# rev1.net
KiCad netlist of a schematic drawn in EAGLE
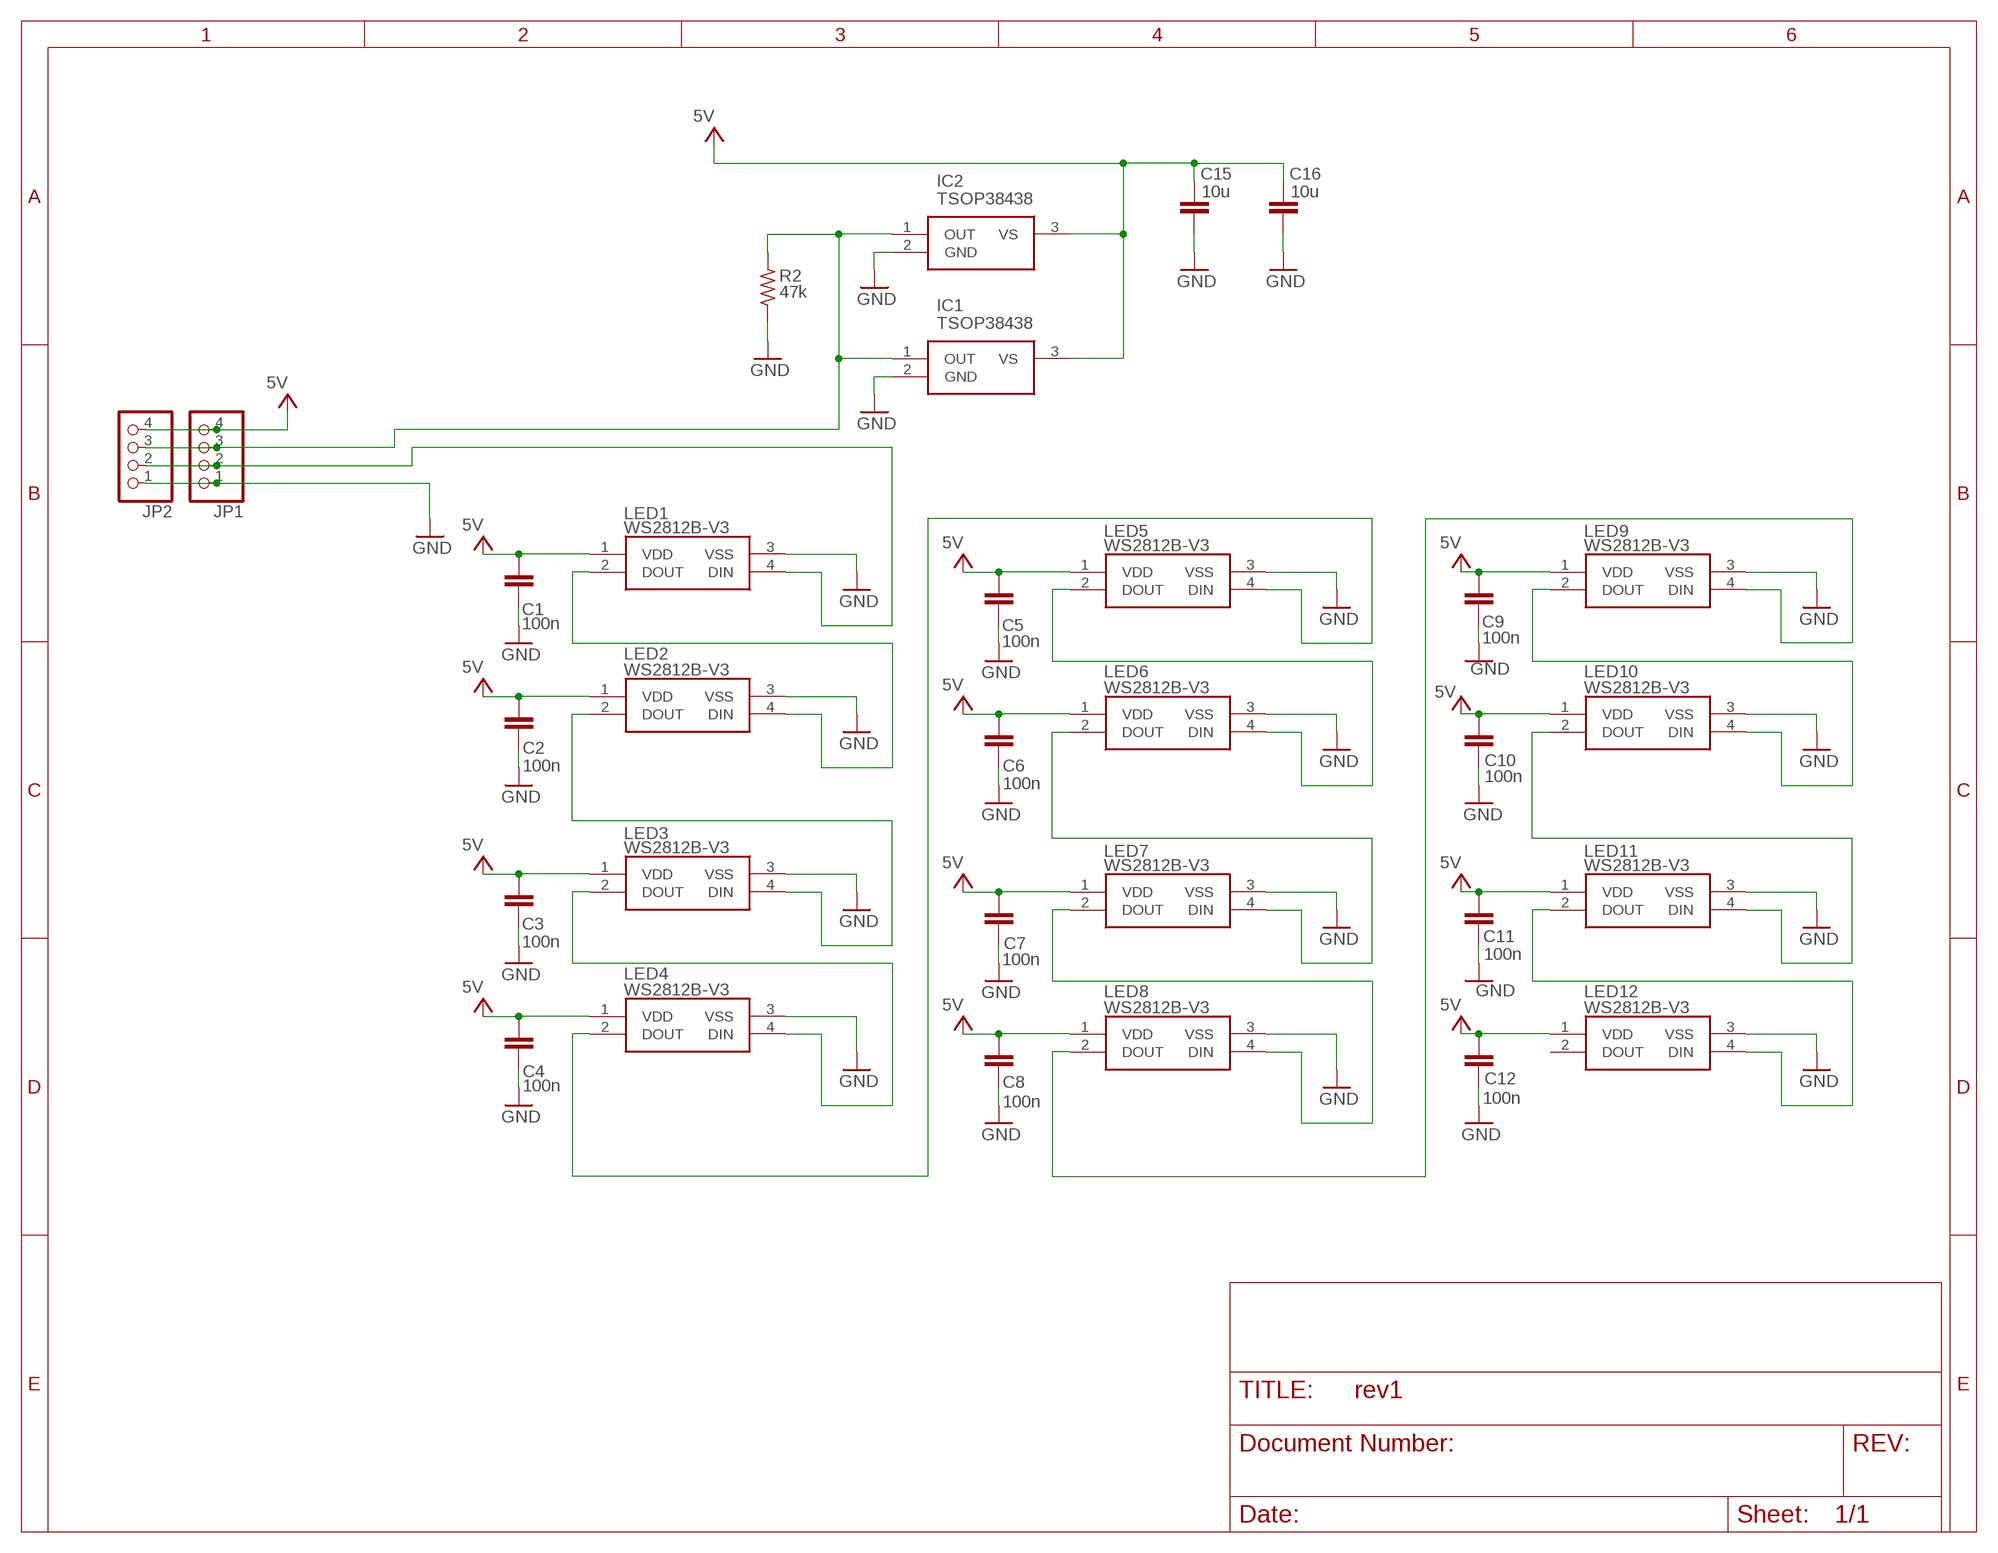
[diagram p0: schematic, sheet 1]

(export (version "E")
  (design (tool "Eeschema 10.0.6"))
  (components
    (comp (ref "C1")
      (value "100n")
      (footprint "eagle-import:C0805")
      (libsource (lib "eagle-import") (part "CAP_SMD0805"))
    )
    (comp (ref "C2")
      (value "100n")
      (footprint "eagle-import:C0805")
      (libsource (lib "eagle-import") (part "CAP_SMD0805"))
    )
    (comp (ref "C3")
      (value "100n")
      (footprint "eagle-import:C0805")
      (libsource (lib "eagle-import") (part "CAP_SMD0805"))
    )
    (comp (ref "C4")
      (value "100n")
      (footprint "eagle-import:C0805")
      (libsource (lib "eagle-import") (part "CAP_SMD0805"))
    )
    (comp (ref "C5")
      (value "100n")
      (footprint "eagle-import:C0805")
      (libsource (lib "eagle-import") (part "CAP_SMD0805"))
    )
    (comp (ref "C6")
      (value "100n")
      (footprint "eagle-import:C0805")
      (libsource (lib "eagle-import") (part "CAP_SMD0805"))
    )
    (comp (ref "C7")
      (value "100n")
      (footprint "eagle-import:C0805")
      (libsource (lib "eagle-import") (part "CAP_SMD0805"))
    )
    (comp (ref "C8")
      (value "100n")
      (footprint "eagle-import:C0805")
      (libsource (lib "eagle-import") (part "CAP_SMD0805"))
    )
    (comp (ref "C9")
      (value "100n")
      (footprint "eagle-import:C0805")
      (libsource (lib "eagle-import") (part "CAP_SMD0805"))
    )
    (comp (ref "C10")
      (value "100n")
      (footprint "eagle-import:C0805")
      (libsource (lib "eagle-import") (part "CAP_SMD0805"))
    )
    (comp (ref "C11")
      (value "100n")
      (footprint "eagle-import:C0805")
      (libsource (lib "eagle-import") (part "CAP_SMD0805"))
    )
    (comp (ref "C12")
      (value "100n")
      (footprint "eagle-import:C0805")
      (libsource (lib "eagle-import") (part "CAP_SMD0805"))
    )
    (comp (ref "C15")
      (value "10u")
      (footprint "eagle-import:C0805")
      (libsource (lib "eagle-import") (part "CAP_SMD0805"))
    )
    (comp (ref "C16")
      (value "10u")
      (footprint "eagle-import:C0805")
      (libsource (lib "eagle-import") (part "CAP_SMD0805"))
    )
    (comp (ref "IC1")
      (value "TSOP38438")
      (footprint "eagle-import:TSOP38238")
      (fields (field (name "MOUSER_PART_NUMBER") "78-TSOP38438") (field (name "RS_PART_NUMBER") "7085092P"))
      (libsource (lib "eagle-import") (part "TSOP38438"))
    )
    (comp (ref "IC2")
      (value "TSOP38438")
      (footprint "eagle-import:TSOP38238")
      (fields (field (name "MOUSER_PART_NUMBER") "78-TSOP38438") (field (name "RS_PART_NUMBER") "7085092P"))
      (libsource (lib "eagle-import") (part "TSOP38438"))
    )
    (comp (ref "JP1")
      (value "PINHD-1X4")
      (footprint "eagle-import:1X04")
      (libsource (lib "eagle-import") (part "PINHD-1X4"))
    )
    (comp (ref "JP2")
      (value "PINHD-1X4")
      (footprint "eagle-import:1X04")
      (libsource (lib "eagle-import") (part "PINHD-1X4"))
    )
    (comp (ref "LED1")
      (value "WS2812B-V3")
      (footprint "eagle-import:WS2812BV3")
      (libsource (lib "eagle-import") (part "WS2812B-V3"))
    )
    (comp (ref "LED2")
      (value "WS2812B-V3")
      (footprint "eagle-import:WS2812BV3")
      (libsource (lib "eagle-import") (part "WS2812B-V3"))
    )
    (comp (ref "LED3")
      (value "WS2812B-V3")
      (footprint "eagle-import:WS2812BV3")
      (libsource (lib "eagle-import") (part "WS2812B-V3"))
    )
    (comp (ref "LED4")
      (value "WS2812B-V3")
      (footprint "eagle-import:WS2812BV3")
      (libsource (lib "eagle-import") (part "WS2812B-V3"))
    )
    (comp (ref "LED5")
      (value "WS2812B-V3")
      (footprint "eagle-import:WS2812BV3")
      (libsource (lib "eagle-import") (part "WS2812B-V3"))
    )
    (comp (ref "LED6")
      (value "WS2812B-V3")
      (footprint "eagle-import:WS2812BV3")
      (libsource (lib "eagle-import") (part "WS2812B-V3"))
    )
    (comp (ref "LED7")
      (value "WS2812B-V3")
      (footprint "eagle-import:WS2812BV3")
      (libsource (lib "eagle-import") (part "WS2812B-V3"))
    )
    (comp (ref "LED8")
      (value "WS2812B-V3")
      (footprint "eagle-import:WS2812BV3")
      (libsource (lib "eagle-import") (part "WS2812B-V3"))
    )
    (comp (ref "LED9")
      (value "WS2812B-V3")
      (footprint "eagle-import:WS2812BV3")
      (libsource (lib "eagle-import") (part "WS2812B-V3"))
    )
    (comp (ref "LED10")
      (value "WS2812B-V3")
      (footprint "eagle-import:WS2812BV3")
      (libsource (lib "eagle-import") (part "WS2812B-V3"))
    )
    (comp (ref "LED11")
      (value "WS2812B-V3")
      (footprint "eagle-import:WS2812BV3")
      (libsource (lib "eagle-import") (part "WS2812B-V3"))
    )
    (comp (ref "LED12")
      (value "WS2812B-V3")
      (footprint "eagle-import:WS2812BV3")
      (libsource (lib "eagle-import") (part "WS2812B-V3"))
    )
    (comp (ref "R2")
      (value "47k")
      (footprint "eagle-import:R0805")
      (libsource (lib "eagle-import") (part "RES_SMD0805"))
    )
  )
  (nets
    (net (code "1") (name "5V") (class "Default")
      (node (ref "C1") (pin "2") (pinfunction "2_2") (pintype "passive"))
      (node (ref "C10") (pin "1") (pinfunction "1_1") (pintype "passive"))
      (node (ref "C11") (pin "2") (pinfunction "2_2") (pintype "passive"))
      (node (ref "C12") (pin "1") (pinfunction "1_1") (pintype "passive"))
      (node (ref "C15") (pin "2") (pinfunction "2_2") (pintype "passive"))
      (node (ref "C16") (pin "2") (pinfunction "2_2") (pintype "passive"))
      (node (ref "C2") (pin "1") (pinfunction "1_1") (pintype "passive"))
      (node (ref "C3") (pin "2") (pinfunction "2_2") (pintype "passive"))
      (node (ref "C4") (pin "1") (pinfunction "1_1") (pintype "passive"))
      (node (ref "C5") (pin "2") (pinfunction "2_2") (pintype "passive"))
      (node (ref "C6") (pin "1") (pinfunction "1_1") (pintype "passive"))
      (node (ref "C7") (pin "2") (pinfunction "2_2") (pintype "passive"))
      (node (ref "C8") (pin "1") (pinfunction "1_1") (pintype "passive"))
      (node (ref "C9") (pin "2") (pinfunction "2_2") (pintype "passive"))
      (node (ref "IC1") (pin "3") (pinfunction "VS_3") (pintype "bidirectional"))
      (node (ref "IC2") (pin "3") (pinfunction "VS_3") (pintype "bidirectional"))
      (node (ref "JP1") (pin "4") (pinfunction "4_4") (pintype "passive"))
      (node (ref "JP2") (pin "4") (pinfunction "4_4") (pintype "passive"))
      (node (ref "LED1") (pin "1") (pinfunction "VDD_1") (pintype "bidirectional"))
      (node (ref "LED10") (pin "1") (pinfunction "VDD_1") (pintype "bidirectional"))
      (node (ref "LED11") (pin "1") (pinfunction "VDD_1") (pintype "bidirectional"))
      (node (ref "LED12") (pin "1") (pinfunction "VDD_1") (pintype "bidirectional"))
      (node (ref "LED2") (pin "1") (pinfunction "VDD_1") (pintype "bidirectional"))
      (node (ref "LED3") (pin "1") (pinfunction "VDD_1") (pintype "bidirectional"))
      (node (ref "LED4") (pin "1") (pinfunction "VDD_1") (pintype "bidirectional"))
      (node (ref "LED5") (pin "1") (pinfunction "VDD_1") (pintype "bidirectional"))
      (node (ref "LED6") (pin "1") (pinfunction "VDD_1") (pintype "bidirectional"))
      (node (ref "LED7") (pin "1") (pinfunction "VDD_1") (pintype "bidirectional"))
      (node (ref "LED8") (pin "1") (pinfunction "VDD_1") (pintype "bidirectional"))
      (node (ref "LED9") (pin "1") (pinfunction "VDD_1") (pintype "bidirectional"))
    )
    (net (code "2") (name "GND") (class "Default")
      (node (ref "C1") (pin "1") (pinfunction "1_1") (pintype "passive"))
      (node (ref "C10") (pin "2") (pinfunction "2_2") (pintype "passive"))
      (node (ref "C11") (pin "1") (pinfunction "1_1") (pintype "passive"))
      (node (ref "C12") (pin "2") (pinfunction "2_2") (pintype "passive"))
      (node (ref "C15") (pin "1") (pinfunction "1_1") (pintype "passive"))
      (node (ref "C16") (pin "1") (pinfunction "1_1") (pintype "passive"))
      (node (ref "C2") (pin "2") (pinfunction "2_2") (pintype "passive"))
      (node (ref "C3") (pin "1") (pinfunction "1_1") (pintype "passive"))
      (node (ref "C4") (pin "2") (pinfunction "2_2") (pintype "passive"))
      (node (ref "C5") (pin "1") (pinfunction "1_1") (pintype "passive"))
      (node (ref "C6") (pin "2") (pinfunction "2_2") (pintype "passive"))
      (node (ref "C7") (pin "1") (pinfunction "1_1") (pintype "passive"))
      (node (ref "C8") (pin "2") (pinfunction "2_2") (pintype "passive"))
      (node (ref "C9") (pin "1") (pinfunction "1_1") (pintype "passive"))
      (node (ref "IC1") (pin "2") (pinfunction "GND_2") (pintype "bidirectional"))
      (node (ref "IC2") (pin "2") (pinfunction "GND_2") (pintype "bidirectional"))
      (node (ref "JP1") (pin "1") (pinfunction "1_1") (pintype "passive"))
      (node (ref "JP2") (pin "1") (pinfunction "1_1") (pintype "passive"))
      (node (ref "LED1") (pin "3") (pinfunction "VSS_3") (pintype "bidirectional"))
      (node (ref "LED10") (pin "3") (pinfunction "VSS_3") (pintype "bidirectional"))
      (node (ref "LED11") (pin "3") (pinfunction "VSS_3") (pintype "bidirectional"))
      (node (ref "LED12") (pin "3") (pinfunction "VSS_3") (pintype "bidirectional"))
      (node (ref "LED2") (pin "3") (pinfunction "VSS_3") (pintype "bidirectional"))
      (node (ref "LED3") (pin "3") (pinfunction "VSS_3") (pintype "bidirectional"))
      (node (ref "LED4") (pin "3") (pinfunction "VSS_3") (pintype "bidirectional"))
      (node (ref "LED5") (pin "3") (pinfunction "VSS_3") (pintype "bidirectional"))
      (node (ref "LED6") (pin "3") (pinfunction "VSS_3") (pintype "bidirectional"))
      (node (ref "LED7") (pin "3") (pinfunction "VSS_3") (pintype "bidirectional"))
      (node (ref "LED8") (pin "3") (pinfunction "VSS_3") (pintype "bidirectional"))
      (node (ref "LED9") (pin "3") (pinfunction "VSS_3") (pintype "bidirectional"))
      (node (ref "R2") (pin "1") (pinfunction "1_1") (pintype "passive"))
    )
    (net (code "3") (name "Net-(IC1-OUT)") (class "Default")
      (node (ref "IC1") (pin "1") (pinfunction "OUT_1") (pintype "bidirectional"))
      (node (ref "IC2") (pin "1") (pinfunction "OUT_1") (pintype "bidirectional"))
      (node (ref "JP1") (pin "3") (pinfunction "3_3") (pintype "passive"))
      (node (ref "JP2") (pin "3") (pinfunction "3_3") (pintype "passive"))
      (node (ref "R2") (pin "2") (pinfunction "2_2") (pintype "passive"))
    )
    (net (code "4") (name "Net-(LED1-DIN)") (class "Default")
      (node (ref "JP1") (pin "2") (pinfunction "2_2") (pintype "passive"))
      (node (ref "JP2") (pin "2") (pinfunction "2_2") (pintype "passive"))
      (node (ref "LED1") (pin "4") (pinfunction "DIN_4") (pintype "bidirectional"))
    )
    (net (code "5") (name "Net-(LED1-DOUT)") (class "Default")
      (node (ref "LED1") (pin "2") (pinfunction "DOUT_2") (pintype "bidirectional"))
      (node (ref "LED2") (pin "4") (pinfunction "DIN_4") (pintype "bidirectional"))
    )
    (net (code "6") (name "Net-(LED2-DOUT)") (class "Default")
      (node (ref "LED2") (pin "2") (pinfunction "DOUT_2") (pintype "bidirectional"))
      (node (ref "LED3") (pin "4") (pinfunction "DIN_4") (pintype "bidirectional"))
    )
    (net (code "7") (name "Net-(LED3-DOUT)") (class "Default")
      (node (ref "LED3") (pin "2") (pinfunction "DOUT_2") (pintype "bidirectional"))
      (node (ref "LED4") (pin "4") (pinfunction "DIN_4") (pintype "bidirectional"))
    )
    (net (code "8") (name "Net-(LED4-DOUT)") (class "Default")
      (node (ref "LED4") (pin "2") (pinfunction "DOUT_2") (pintype "bidirectional"))
      (node (ref "LED5") (pin "4") (pinfunction "DIN_4") (pintype "bidirectional"))
    )
    (net (code "9") (name "Net-(LED5-DOUT)") (class "Default")
      (node (ref "LED5") (pin "2") (pinfunction "DOUT_2") (pintype "bidirectional"))
      (node (ref "LED6") (pin "4") (pinfunction "DIN_4") (pintype "bidirectional"))
    )
    (net (code "10") (name "Net-(LED6-DOUT)") (class "Default")
      (node (ref "LED6") (pin "2") (pinfunction "DOUT_2") (pintype "bidirectional"))
      (node (ref "LED7") (pin "4") (pinfunction "DIN_4") (pintype "bidirectional"))
    )
    (net (code "11") (name "Net-(LED7-DOUT)") (class "Default")
      (node (ref "LED7") (pin "2") (pinfunction "DOUT_2") (pintype "bidirectional"))
      (node (ref "LED8") (pin "4") (pinfunction "DIN_4") (pintype "bidirectional"))
    )
    (net (code "12") (name "Net-(LED8-DOUT)") (class "Default")
      (node (ref "LED8") (pin "2") (pinfunction "DOUT_2") (pintype "bidirectional"))
      (node (ref "LED9") (pin "4") (pinfunction "DIN_4") (pintype "bidirectional"))
    )
    (net (code "13") (name "Net-(LED10-DIN)") (class "Default")
      (node (ref "LED10") (pin "4") (pinfunction "DIN_4") (pintype "bidirectional"))
      (node (ref "LED9") (pin "2") (pinfunction "DOUT_2") (pintype "bidirectional"))
    )
    (net (code "14") (name "Net-(LED10-DOUT)") (class "Default")
      (node (ref "LED10") (pin "2") (pinfunction "DOUT_2") (pintype "bidirectional"))
      (node (ref "LED11") (pin "4") (pinfunction "DIN_4") (pintype "bidirectional"))
    )
    (net (code "15") (name "Net-(LED11-DOUT)") (class "Default")
      (node (ref "LED11") (pin "2") (pinfunction "DOUT_2") (pintype "bidirectional"))
      (node (ref "LED12") (pin "4") (pinfunction "DIN_4") (pintype "bidirectional"))
    )
    (net (code "16") (name "unconnected-(LED12-DOUT-Pad2)") (class "Default")
      (node (ref "LED12") (pin "2") (pinfunction "DOUT_2") (pintype "bidirectional"))
    )
  )
)
